# SCH_CanSat2024_v5_1.net
KiCad netlist of a schematic drawn in EasyEDA
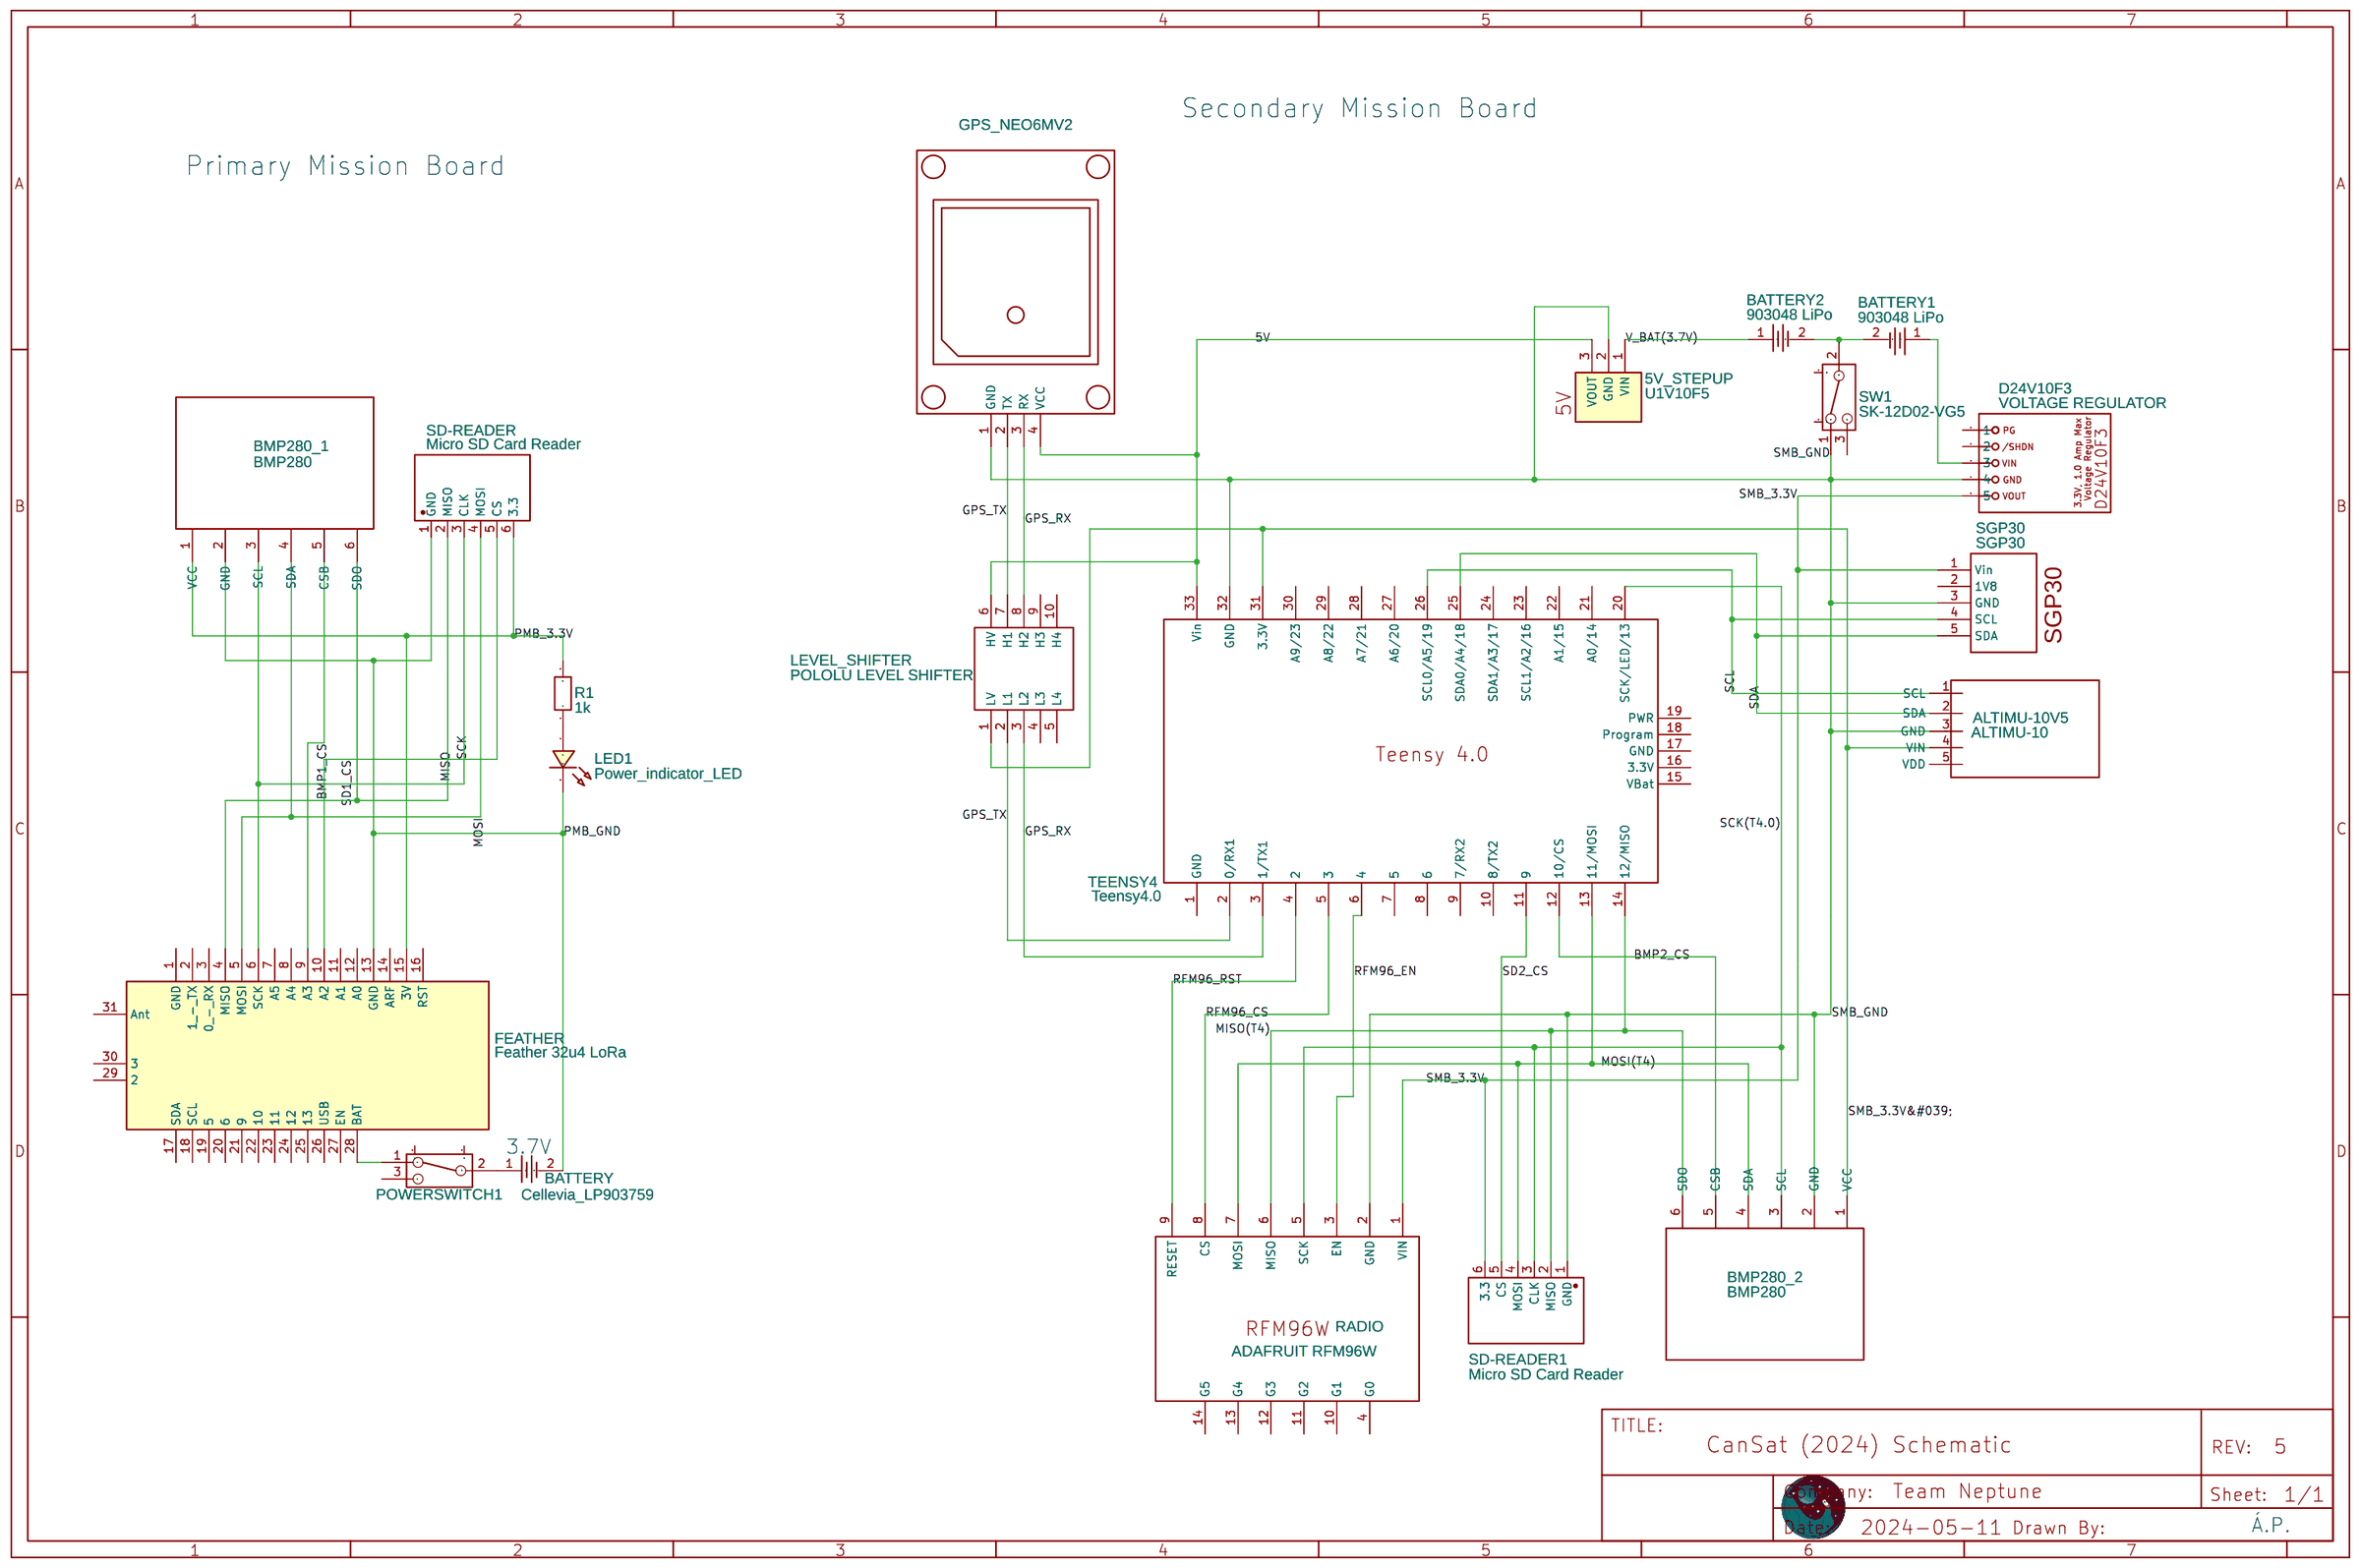
[diagram p0: schematic sheet]

(export (version "E")
  (design (tool "Eeschema 10.0.6"))
  (components
    (comp (ref "5V_STEPUP") (value "U1V10F5") (libsource (lib "") (part "U1V10F5 COPY")))
    (comp (ref "ALTIMU-10V5") (value "ALTIMU-10") (libsource (lib "") (part "ALTIMU-10")))
    (comp (ref "BATTERY")
      (value "Cellevia_LP903759")
      (fields (field (name "Manufacturer Part") "CR1220-2") (field (name "Manufacturer") "Q&J"))
      (libsource (lib "") (part "CR1220-2_1"))
    )
    (comp (ref "BATTERY1")
      (value "903048 LiPo")
      (fields (field (name "Manufacturer Part") "CR1220-2") (field (name "Manufacturer") "Q&J"))
      (libsource (lib "") (part "CR1220-2"))
    )
    (comp (ref "BATTERY2")
      (value "903048 LiPo")
      (fields (field (name "Manufacturer Part") "CR1220-2") (field (name "Manufacturer") "Q&J"))
      (libsource (lib "") (part "CR1220-2_1"))
    )
    (comp (ref "BMP280_1") (value "BMP280") (libsource (lib "") (part "BMP280_1")))
    (comp (ref "BMP280_2") (value "BMP280") (libsource (lib "") (part "BMP280")))
    (comp (ref "D24V10F3")
      (value "VOLTAGE REGULATOR")
      (fields (field (name "Manufacturer Part") "HDR-M-2.54_1x6"))
      (libsource (lib "") (part "D24V10F5 VOLTAGE REGULATOR"))
    )
    (comp (ref "FEATHER") (value "Feather 32u4 LoRa") (libsource (lib "") (part "Feather 32u4 LoRa")))
    (comp (ref "GPS_NEO6MV2") (value "Cheap GPS") (libsource (lib "") (part "Cheap GPS")))
    (comp (ref "LED1")
      (value "Power_indicator_LED")
      (fields
        (field (name "Manufacturer Part") "19-217/R6C-AL1M2VY/3T")
        (field (name "Manufacturer") "EVERLIGHT(台湾亿光)")
      )
      (libsource (lib "") (part "LED-0603_R"))
    )
    (comp (ref "LEVEL_SHIFTER")
      (value "POLOLU LEVEL SHIFTER")
      (fields (field (name "Manufacturer Part") "pololu #2595") (field (name "Manufacturer") "POLOLU"))
      (libsource (lib "") (part "pololu_level_shifter"))
    )
    (comp (ref "POWERSWITCH1")
      (value "SWITCH")
      (fields
        (field (name "Manufacturer Part") "SK-12D02-VG5")
        (field (name "Manufacturer") "Rectangular Connectors - Contacts")
      )
      (libsource (lib "") (part "SK-12D02-VG5"))
    )
    (comp (ref "R1") (value "1k") (libsource (lib "") (part "R_0603_EU")))
    (comp (ref "RADIO")
      (value "ADAFRUIT RFM96W")
      (fields (field (name "Manufacturer Part") "RFM96W") (field (name "Manufacturer") "HopeRF"))
      (libsource (lib "") (part "ADAFRUIT RFM96W BOARD COPY"))
    )
    (comp (ref "SD-READER")
      (value "Micro SD Card Reader")
      (fields
        (field (name "Manufacturer Part") "SD card reader 17.9x17.9")
        (field (name "Manufacturer") "ShengYang")
      )
      (libsource (lib "") (part "Micro SD Card Reader"))
    )
    (comp (ref "SD-READER1")
      (value "Micro SD Card Reader")
      (fields
        (field (name "Manufacturer Part") "SD card reader 17.9x17.9")
        (field (name "Manufacturer") "ShengYang")
      )
      (libsource (lib "") (part "Micro SD Card Reader_1"))
    )
    (comp (ref "SGP30")
      (value "SGP30")
      (fields (field (name "Manufacturer Part") "Adafruit"))
      (libsource (lib "") (part "SGP30"))
    )
    (comp (ref "SW1")
      (value "SK-12D02-VG5")
      (fields (field (name "Manufacturer") "Rectangular Connectors - Contacts"))
      (libsource (lib "") (part "SK-12D02-VG5_1"))
    )
    (comp (ref "TEENSY4")
      (value "Teensy4.0")
      (fields (field (name "Manufacturer") "PJRC"))
      (libsource (lib "") (part "Teensy4.0"))
    )
  )
  (nets
    (net (code "1") (name "/5V") (class "Default")
      (node (ref "5V_STEPUP") (pin "3") (pinfunction "VOUT_3") (pintype "unspecified"))
      (node (ref "GPS_NEO6MV2") (pin "4") (pinfunction "VCC_4") (pintype "unspecified"))
      (node (ref "LEVEL_SHIFTER") (pin "6") (pinfunction "HV_6") (pintype "unspecified"))
      (node (ref "TEENSY4") (pin "33") (pinfunction "Vin_33") (pintype "unspecified"))
    )
    (net (code "2") (name "/BMP1_CS") (class "Default")
      (node (ref "BMP280_1") (pin "5") (pinfunction "CSB_5") (pintype "unspecified"))
      (node (ref "FEATHER") (pin "9") (pinfunction "A3_9") (pintype "unspecified"))
    )
    (net (code "3") (name "/BMP2_CS") (class "Default")
      (node (ref "BMP280_2") (pin "5") (pinfunction "CSB_5") (pintype "unspecified"))
      (node (ref "TEENSY4") (pin "12") (pinfunction "10/CS_12") (pintype "unspecified"))
    )
    (net (code "4") (name "/GPS_RX") (class "Default")
      (node (ref "GPS_NEO6MV2") (pin "3") (pinfunction "RX_3") (pintype "unspecified"))
      (node (ref "LEVEL_SHIFTER") (pin "3") (pinfunction "L2_3") (pintype "unspecified"))
      (node (ref "LEVEL_SHIFTER") (pin "8") (pinfunction "H2_8") (pintype "unspecified"))
      (node (ref "TEENSY4") (pin "3") (pinfunction "1/TX1_3") (pintype "unspecified"))
    )
    (net (code "5") (name "/GPS_TX") (class "Default")
      (node (ref "GPS_NEO6MV2") (pin "2") (pinfunction "TX_2") (pintype "unspecified"))
      (node (ref "LEVEL_SHIFTER") (pin "2") (pinfunction "L1_2") (pintype "unspecified"))
      (node (ref "LEVEL_SHIFTER") (pin "7") (pinfunction "H1_7") (pintype "unspecified"))
      (node (ref "TEENSY4") (pin "2") (pinfunction "0/RX1_2") (pintype "unspecified"))
    )
    (net (code "6") (name "/MISO") (class "Default")
      (node (ref "BMP280_1") (pin "6") (pinfunction "SDO_6") (pintype "unspecified"))
      (node (ref "FEATHER") (pin "4") (pinfunction "MISO_4") (pintype "unspecified"))
      (node (ref "SD-READER") (pin "2") (pinfunction "MISO_2") (pintype "unspecified"))
    )
    (net (code "7") (name "/MISO(T4)") (class "Default")
      (node (ref "BMP280_2") (pin "6") (pinfunction "SDO_6") (pintype "unspecified"))
      (node (ref "RADIO") (pin "6") (pinfunction "MISO_6") (pintype "unspecified"))
      (node (ref "SD-READER1") (pin "2") (pinfunction "MISO_2") (pintype "unspecified"))
      (node (ref "TEENSY4") (pin "14") (pinfunction "12/MISO_14") (pintype "unspecified"))
    )
    (net (code "8") (name "/MOSI") (class "Default")
      (node (ref "BMP280_1") (pin "4") (pinfunction "SDA_4") (pintype "unspecified"))
      (node (ref "FEATHER") (pin "5") (pinfunction "MOSI_5") (pintype "unspecified"))
      (node (ref "SD-READER") (pin "4") (pinfunction "MOSI_4") (pintype "unspecified"))
    )
    (net (code "9") (name "/MOSI(T4)") (class "Default")
      (node (ref "BMP280_2") (pin "4") (pinfunction "SDA_4") (pintype "unspecified"))
      (node (ref "RADIO") (pin "7") (pinfunction "MOSI_7") (pintype "unspecified"))
      (node (ref "SD-READER1") (pin "4") (pinfunction "MOSI_4") (pintype "unspecified"))
      (node (ref "TEENSY4") (pin "13") (pinfunction "11/MOSI_13") (pintype "unspecified"))
    )
    (net (code "10") (name "/PMB_3.3V") (class "Default")
      (node (ref "BMP280_1") (pin "1") (pinfunction "VCC_1") (pintype "unspecified"))
      (node (ref "FEATHER") (pin "15") (pinfunction "3V_15") (pintype "unspecified"))
      (node (ref "R1") (pin "2") (pinfunction "2_2") (pintype "unspecified"))
      (node (ref "SD-READER") (pin "6") (pinfunction "3.3_6") (pintype "unspecified"))
    )
    (net (code "11") (name "/PMB_GND") (class "Default")
      (node (ref "BATTERY") (pin "2") (pinfunction "2_2") (pintype "input"))
      (node (ref "BMP280_1") (pin "2") (pinfunction "GND_2") (pintype "unspecified"))
      (node (ref "FEATHER") (pin "13") (pinfunction "GND_13") (pintype "unspecified"))
      (node (ref "LED1") (pin "2") (pinfunction "2_2") (pintype "unspecified"))
      (node (ref "SD-READER") (pin "1") (pinfunction "GND_1") (pintype "unspecified"))
    )
    (net (code "12") (name "/RFM96_CS") (class "Default")
      (node (ref "RADIO") (pin "8") (pinfunction "CS_8") (pintype "unspecified"))
      (node (ref "TEENSY4") (pin "5") (pinfunction "3_5") (pintype "unspecified"))
    )
    (net (code "13") (name "/RFM96_EN") (class "Default")
      (node (ref "RADIO") (pin "3") (pinfunction "EN_3") (pintype "unspecified"))
      (node (ref "TEENSY4") (pin "6") (pinfunction "4_6") (pintype "unspecified"))
    )
    (net (code "14") (name "/RFM96_RST") (class "Default")
      (node (ref "RADIO") (pin "9") (pinfunction "RESET_9") (pintype "unspecified"))
      (node (ref "TEENSY4") (pin "4") (pinfunction "2_4") (pintype "unspecified"))
    )
    (net (code "15") (name "/SCK") (class "Default")
      (node (ref "BMP280_1") (pin "3") (pinfunction "SCL_3") (pintype "unspecified"))
      (node (ref "FEATHER") (pin "6") (pinfunction "SCK_6") (pintype "unspecified"))
      (node (ref "SD-READER") (pin "3") (pinfunction "CLK_3") (pintype "unspecified"))
    )
    (net (code "16") (name "/SCK(T4.0)") (class "Default")
      (node (ref "BMP280_2") (pin "3") (pinfunction "SCL_3") (pintype "unspecified"))
      (node (ref "RADIO") (pin "5") (pinfunction "SCK_5") (pintype "unspecified"))
      (node (ref "SD-READER1") (pin "3") (pinfunction "CLK_3") (pintype "unspecified"))
      (node (ref "TEENSY4") (pin "20") (pinfunction "SCK/LED/13_20") (pintype "unspecified"))
    )
    (net (code "17") (name "/SCL") (class "Default")
      (node (ref "ALTIMU-10V5") (pin "1") (pinfunction "SCL_1") (pintype "unspecified"))
      (node (ref "SGP30") (pin "4") (pinfunction "SCL_4") (pintype "unspecified"))
      (node (ref "TEENSY4") (pin "26") (pinfunction "SCL0/A5/19_26") (pintype "unspecified"))
    )
    (net (code "18") (name "/SD1_CS") (class "Default")
      (node (ref "FEATHER") (pin "10") (pinfunction "A2_10") (pintype "unspecified"))
      (node (ref "SD-READER") (pin "5") (pinfunction "CS_5") (pintype "unspecified"))
    )
    (net (code "19") (name "/SD2_CS") (class "Default")
      (node (ref "SD-READER1") (pin "5") (pinfunction "CS_5") (pintype "unspecified"))
      (node (ref "TEENSY4") (pin "11") (pinfunction "9_11") (pintype "unspecified"))
    )
    (net (code "20") (name "/SDA") (class "Default")
      (node (ref "ALTIMU-10V5") (pin "2") (pinfunction "SDA_2") (pintype "unspecified"))
      (node (ref "SGP30") (pin "5") (pinfunction "SDA_5") (pintype "unspecified"))
      (node (ref "TEENSY4") (pin "25") (pinfunction "SDA0/A4/18_25") (pintype "unspecified"))
    )
    (net (code "21") (name "/SMB_3.3V") (class "Default")
      (node (ref "D24V10F3") (pin "5") (pinfunction "5_5") (pintype "unspecified"))
      (node (ref "RADIO") (pin "1") (pinfunction "VIN_1") (pintype "unspecified"))
      (node (ref "SD-READER1") (pin "6") (pinfunction "3.3_6") (pintype "unspecified"))
      (node (ref "SGP30") (pin "1") (pinfunction "Vin_1") (pintype "unspecified"))
    )
    (net (code "22") (name "/SMB_3.3V&#039;") (class "Default")
      (node (ref "ALTIMU-10V5") (pin "4") (pinfunction "VIN_4") (pintype "unspecified"))
      (node (ref "BMP280_2") (pin "1") (pinfunction "VCC_1") (pintype "unspecified"))
      (node (ref "LEVEL_SHIFTER") (pin "1") (pinfunction "LV_1") (pintype "unspecified"))
      (node (ref "TEENSY4") (pin "31") (pinfunction "3.3V_31") (pintype "unspecified"))
    )
    (net (code "23") (name "/SMB_GND") (class "Default")
      (node (ref "5V_STEPUP") (pin "2") (pinfunction "GND_2") (pintype "unspecified"))
      (node (ref "ALTIMU-10V5") (pin "3") (pinfunction "GND_3") (pintype "unspecified"))
      (node (ref "BMP280_2") (pin "2") (pinfunction "GND_2") (pintype "unspecified"))
      (node (ref "D24V10F3") (pin "4") (pinfunction "4_4") (pintype "unspecified"))
      (node (ref "GPS_NEO6MV2") (pin "1") (pinfunction "GND_1") (pintype "unspecified"))
      (node (ref "RADIO") (pin "2") (pinfunction "GND_2") (pintype "unspecified"))
      (node (ref "SD-READER1") (pin "1") (pinfunction "GND_1") (pintype "unspecified"))
      (node (ref "SGP30") (pin "3") (pinfunction "GND_3") (pintype "unspecified"))
      (node (ref "SW1") (pin "1") (pinfunction "1_1") (pintype "unspecified"))
      (node (ref "TEENSY4") (pin "32") (pinfunction "GND_32") (pintype "unspecified"))
    )
    (net (code "24") (name "/V_BAT(3.7V)") (class "Default")
      (node (ref "5V_STEPUP") (pin "1") (pinfunction "VIN_1") (pintype "unspecified"))
      (node (ref "BATTERY2") (pin "1") (pinfunction "1_1") (pintype "input"))
    )
    (net (code "25") (name "Net-(BATTERY-Pad1)") (class "Default")
      (node (ref "BATTERY") (pin "1") (pinfunction "1_1") (pintype "input"))
      (node (ref "POWERSWITCH1") (pin "2") (pinfunction "2_2") (pintype "unspecified"))
    )
    (net (code "26") (name "Net-(BATTERY1-Pad1)") (class "Default")
      (node (ref "BATTERY1") (pin "1") (pinfunction "1_1") (pintype "input"))
      (node (ref "D24V10F3") (pin "3") (pinfunction "3_3") (pintype "unspecified"))
    )
    (net (code "27") (name "Net-(BATTERY1-Pad2)") (class "Default")
      (node (ref "BATTERY1") (pin "2") (pinfunction "2_2") (pintype "input"))
      (node (ref "BATTERY2") (pin "2") (pinfunction "2_2") (pintype "input"))
      (node (ref "SW1") (pin "2") (pinfunction "2_2") (pintype "unspecified"))
    )
    (net (code "28") (name "Net-(FEATHER-BAT)") (class "Default")
      (node (ref "FEATHER") (pin "28") (pinfunction "BAT_28") (pintype "unspecified"))
      (node (ref "POWERSWITCH1") (pin "1") (pinfunction "1_1") (pintype "unspecified"))
    )
    (net (code "29") (name "Net-(LED1-Pad1)") (class "Default")
      (node (ref "LED1") (pin "1") (pinfunction "1_1") (pintype "unspecified"))
      (node (ref "R1") (pin "1") (pinfunction "1_1") (pintype "unspecified"))
    )
    (net (code "30") (name "unconnected-(ALTIMU-10V5-VDD-Pad5)") (class "Default")
      (node (ref "ALTIMU-10V5") (pin "5") (pinfunction "VDD_5") (pintype "unspecified"))
    )
    (net (code "31") (name "unconnected-(D24V10F3-Pad1)") (class "Default")
      (node (ref "D24V10F3") (pin "1") (pinfunction "1_1") (pintype "unspecified"))
    )
    (net (code "32") (name "unconnected-(D24V10F3-Pad2)") (class "Default")
      (node (ref "D24V10F3") (pin "2") (pinfunction "2_2") (pintype "unspecified"))
    )
    (net (code "33") (name "unconnected-(FEATHER-0_-_RX-Pad3)") (class "Default")
      (node (ref "FEATHER") (pin "3") (pinfunction "0_-_RX_3") (pintype "unspecified"))
    )
    (net (code "34") (name "unconnected-(FEATHER-1_-_TX-Pad2)") (class "Default")
      (node (ref "FEATHER") (pin "2") (pinfunction "1_-_TX_2") (pintype "unspecified"))
    )
    (net (code "35") (name "unconnected-(FEATHER-2-Pad29)") (class "Default")
      (node (ref "FEATHER") (pin "29") (pinfunction "2_29") (pintype "unspecified"))
    )
    (net (code "36") (name "unconnected-(FEATHER-3-Pad30)") (class "Default")
      (node (ref "FEATHER") (pin "30") (pinfunction "3_30") (pintype "unspecified"))
    )
    (net (code "37") (name "unconnected-(FEATHER-5-Pad19)") (class "Default")
      (node (ref "FEATHER") (pin "19") (pinfunction "5_19") (pintype "unspecified"))
    )
    (net (code "38") (name "unconnected-(FEATHER-6-Pad20)") (class "Default")
      (node (ref "FEATHER") (pin "20") (pinfunction "6_20") (pintype "unspecified"))
    )
    (net (code "39") (name "unconnected-(FEATHER-9-Pad21)") (class "Default")
      (node (ref "FEATHER") (pin "21") (pinfunction "9_21") (pintype "unspecified"))
    )
    (net (code "40") (name "unconnected-(FEATHER-10-Pad22)") (class "Default")
      (node (ref "FEATHER") (pin "22") (pinfunction "10_22") (pintype "unspecified"))
    )
    (net (code "41") (name "unconnected-(FEATHER-11-Pad23)") (class "Default")
      (node (ref "FEATHER") (pin "23") (pinfunction "11_23") (pintype "unspecified"))
    )
    (net (code "42") (name "unconnected-(FEATHER-12-Pad24)") (class "Default")
      (node (ref "FEATHER") (pin "24") (pinfunction "12_24") (pintype "unspecified"))
    )
    (net (code "43") (name "unconnected-(FEATHER-13-Pad25)") (class "Default")
      (node (ref "FEATHER") (pin "25") (pinfunction "13_25") (pintype "unspecified"))
    )
    (net (code "44") (name "unconnected-(FEATHER-A0-Pad12)") (class "Default")
      (node (ref "FEATHER") (pin "12") (pinfunction "A0_12") (pintype "unspecified"))
    )
    (net (code "45") (name "unconnected-(FEATHER-A1-Pad11)") (class "Default")
      (node (ref "FEATHER") (pin "11") (pinfunction "A1_11") (pintype "unspecified"))
    )
    (net (code "46") (name "unconnected-(FEATHER-A4-Pad8)") (class "Default")
      (node (ref "FEATHER") (pin "8") (pinfunction "A4_8") (pintype "unspecified"))
    )
    (net (code "47") (name "unconnected-(FEATHER-A5-Pad7)") (class "Default")
      (node (ref "FEATHER") (pin "7") (pinfunction "A5_7") (pintype "unspecified"))
    )
    (net (code "48") (name "unconnected-(FEATHER-ARF-Pad14)") (class "Default")
      (node (ref "FEATHER") (pin "14") (pinfunction "ARF_14") (pintype "unspecified"))
    )
    (net (code "49") (name "unconnected-(FEATHER-Ant-Pad31)") (class "Default")
      (node (ref "FEATHER") (pin "31") (pinfunction "Ant_31") (pintype "unspecified"))
    )
    (net (code "50") (name "unconnected-(FEATHER-EN-Pad27)") (class "Default")
      (node (ref "FEATHER") (pin "27") (pinfunction "EN_27") (pintype "unspecified"))
    )
    (net (code "51") (name "unconnected-(FEATHER-GND-Pad1)") (class "Default")
      (node (ref "FEATHER") (pin "1") (pinfunction "GND_1") (pintype "unspecified"))
    )
    (net (code "52") (name "unconnected-(FEATHER-RST-Pad16)") (class "Default")
      (node (ref "FEATHER") (pin "16") (pinfunction "RST_16") (pintype "unspecified"))
    )
    (net (code "53") (name "unconnected-(FEATHER-SCL-Pad18)") (class "Default")
      (node (ref "FEATHER") (pin "18") (pinfunction "SCL_18") (pintype "unspecified"))
    )
    (net (code "54") (name "unconnected-(FEATHER-SDA-Pad17)") (class "Default")
      (node (ref "FEATHER") (pin "17") (pinfunction "SDA_17") (pintype "unspecified"))
    )
    (net (code "55") (name "unconnected-(FEATHER-USB-Pad26)") (class "Default")
      (node (ref "FEATHER") (pin "26") (pinfunction "USB_26") (pintype "unspecified"))
    )
    (net (code "56") (name "unconnected-(LEVEL_SHIFTER-H3-Pad9)") (class "Default")
      (node (ref "LEVEL_SHIFTER") (pin "9") (pinfunction "H3_9") (pintype "unspecified"))
    )
    (net (code "57") (name "unconnected-(LEVEL_SHIFTER-H4-Pad10)") (class "Default")
      (node (ref "LEVEL_SHIFTER") (pin "10") (pinfunction "H4_10") (pintype "unspecified"))
    )
    (net (code "58") (name "unconnected-(LEVEL_SHIFTER-L3-Pad4)") (class "Default")
      (node (ref "LEVEL_SHIFTER") (pin "4") (pinfunction "L3_4") (pintype "unspecified"))
    )
    (net (code "59") (name "unconnected-(LEVEL_SHIFTER-L4-Pad5)") (class "Default")
      (node (ref "LEVEL_SHIFTER") (pin "5") (pinfunction "L4_5") (pintype "unspecified"))
    )
    (net (code "60") (name "unconnected-(POWERSWITCH1-Pad3)") (class "Default")
      (node (ref "POWERSWITCH1") (pin "3") (pinfunction "3_3") (pintype "unspecified"))
    )
    (net (code "61") (name "unconnected-(POWERSWITCH1-Pad4)") (class "Default")
      (node (ref "POWERSWITCH1") (pin "4") (pinfunction "4_4") (pintype "unspecified"))
    )
    (net (code "62") (name "unconnected-(POWERSWITCH1-Pad5)") (class "Default")
      (node (ref "POWERSWITCH1") (pin "5") (pinfunction "5_5") (pintype "unspecified"))
    )
    (net (code "63") (name "unconnected-(RADIO-G0-Pad4)") (class "Default")
      (node (ref "RADIO") (pin "4") (pinfunction "G0_4") (pintype "unspecified"))
    )
    (net (code "64") (name "unconnected-(RADIO-G1-Pad10)") (class "Default")
      (node (ref "RADIO") (pin "10") (pinfunction "G1_10") (pintype "unspecified"))
    )
    (net (code "65") (name "unconnected-(RADIO-G2-Pad11)") (class "Default")
      (node (ref "RADIO") (pin "11") (pinfunction "G2_11") (pintype "unspecified"))
    )
    (net (code "66") (name "unconnected-(RADIO-G3-Pad12)") (class "Default")
      (node (ref "RADIO") (pin "12") (pinfunction "G3_12") (pintype "unspecified"))
    )
    (net (code "67") (name "unconnected-(RADIO-G4-Pad13)") (class "Default")
      (node (ref "RADIO") (pin "13") (pinfunction "G4_13") (pintype "unspecified"))
    )
    (net (code "68") (name "unconnected-(RADIO-G5-Pad14)") (class "Default")
      (node (ref "RADIO") (pin "14") (pinfunction "G5_14") (pintype "unspecified"))
    )
    (net (code "69") (name "unconnected-(SGP30-1V8-Pad2)") (class "Default")
      (node (ref "SGP30") (pin "2") (pinfunction "1V8_2") (pintype "unspecified"))
    )
    (net (code "70") (name "unconnected-(SW1-Pad3)") (class "Default")
      (node (ref "SW1") (pin "3") (pinfunction "3_3") (pintype "unspecified"))
    )
    (net (code "71") (name "unconnected-(SW1-Pad4)") (class "Default")
      (node (ref "SW1") (pin "4") (pinfunction "4_4") (pintype "unspecified"))
    )
    (net (code "72") (name "unconnected-(SW1-Pad5)") (class "Default")
      (node (ref "SW1") (pin "5") (pinfunction "5_5") (pintype "unspecified"))
    )
    (net (code "73") (name "unconnected-(TEENSY4-3.3V-Pad16)") (class "Default")
      (node (ref "TEENSY4") (pin "16") (pinfunction "3.3V_16") (pintype "unspecified"))
    )
    (net (code "74") (name "unconnected-(TEENSY4-5-Pad7)") (class "Default")
      (node (ref "TEENSY4") (pin "7") (pinfunction "5_7") (pintype "unspecified"))
    )
    (net (code "75") (name "unconnected-(TEENSY4-6-Pad8)") (class "Default")
      (node (ref "TEENSY4") (pin "8") (pinfunction "6_8") (pintype "unspecified"))
    )
    (net (code "76") (name "unconnected-(TEENSY4-7{slash}RX2-Pad9)") (class "Default")
      (node (ref "TEENSY4") (pin "9") (pinfunction "7/RX2_9") (pintype "unspecified"))
    )
    (net (code "77") (name "unconnected-(TEENSY4-8{slash}TX2-Pad10)") (class "Default")
      (node (ref "TEENSY4") (pin "10") (pinfunction "8/TX2_10") (pintype "unspecified"))
    )
    (net (code "78") (name "unconnected-(TEENSY4-A0{slash}14-Pad21)") (class "Default")
      (node (ref "TEENSY4") (pin "21") (pinfunction "A0/14_21") (pintype "unspecified"))
    )
    (net (code "79") (name "unconnected-(TEENSY4-A1{slash}15-Pad22)") (class "Default")
      (node (ref "TEENSY4") (pin "22") (pinfunction "A1/15_22") (pintype "unspecified"))
    )
    (net (code "80") (name "unconnected-(TEENSY4-A6{slash}20-Pad27)") (class "Default")
      (node (ref "TEENSY4") (pin "27") (pinfunction "A6/20_27") (pintype "unspecified"))
    )
    (net (code "81") (name "unconnected-(TEENSY4-A7{slash}21-Pad28)") (class "Default")
      (node (ref "TEENSY4") (pin "28") (pinfunction "A7/21_28") (pintype "unspecified"))
    )
    (net (code "82") (name "unconnected-(TEENSY4-A8{slash}22-Pad29)") (class "Default")
      (node (ref "TEENSY4") (pin "29") (pinfunction "A8/22_29") (pintype "unspecified"))
    )
    (net (code "83") (name "unconnected-(TEENSY4-A9{slash}23-Pad30)") (class "Default")
      (node (ref "TEENSY4") (pin "30") (pinfunction "A9/23_30") (pintype "unspecified"))
    )
    (net (code "84") (name "unconnected-(TEENSY4-GND-Pad1)") (class "Default")
      (node (ref "TEENSY4") (pin "1") (pinfunction "GND_1") (pintype "unspecified"))
    )
    (net (code "85") (name "unconnected-(TEENSY4-GND-Pad17)") (class "Default")
      (node (ref "TEENSY4") (pin "17") (pinfunction "GND_17") (pintype "unspecified"))
    )
    (net (code "86") (name "unconnected-(TEENSY4-PWR-Pad19)") (class "Default")
      (node (ref "TEENSY4") (pin "19") (pinfunction "PWR_19") (pintype "unspecified"))
    )
    (net (code "87") (name "unconnected-(TEENSY4-Program-Pad18)") (class "Default")
      (node (ref "TEENSY4") (pin "18") (pinfunction "Program_18") (pintype "unspecified"))
    )
    (net (code "88") (name "unconnected-(TEENSY4-SCL1{slash}A2{slash}16-Pad23)") (class "Default")
      (node (ref "TEENSY4") (pin "23") (pinfunction "SCL1/A2/16_23") (pintype "unspecified"))
    )
    (net (code "89") (name "unconnected-(TEENSY4-SDA1{slash}A3{slash}17-Pad24)") (class "Default")
      (node (ref "TEENSY4") (pin "24") (pinfunction "SDA1/A3/17_24") (pintype "unspecified"))
    )
    (net (code "90") (name "unconnected-(TEENSY4-VBat-Pad15)") (class "Default")
      (node (ref "TEENSY4") (pin "15") (pinfunction "VBat_15") (pintype "unspecified"))
    )
  )
)
